# Power.net
KiCad netlist of a schematic drawn in Altium Designer
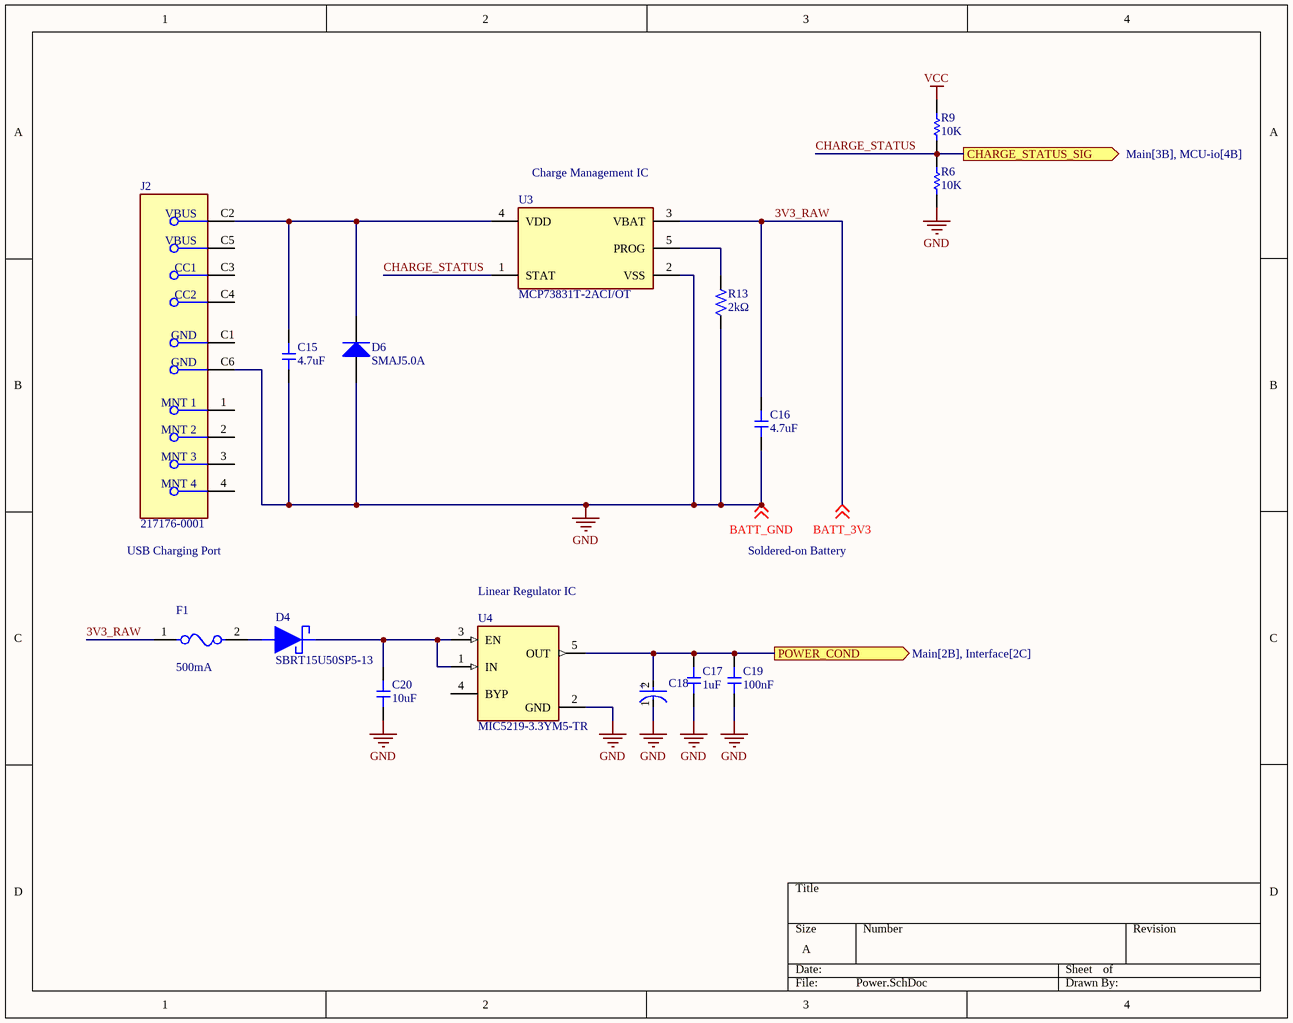
[diagram p0: Power.SchDoc]

(export (version "E")
  (design (tool "Eeschema 10.0.6"))
  (components
    (comp (ref "C15")
      (value "CL10A475KO8NNNC")
      (footprint "CAP-0603")
      (description "Capacitor, Ceramic (MLCC), 4.7uF, ±10%, 16V, X5R, ±10%, SMD 0603")
      (fields
        (field (name "JLCPCB BASIC PART") "Yes")
        (field (name "JLCPCB PART NUMBER") "C19666")
        (field (name "CAPACITANCE") "4.7uF")
      )
      (libsource (lib "JLCCapacitor") (part "CL10A475KO8NNNC"))
    )
    (comp (ref "C16")
      (value "CL10A475KO8NNNC")
      (footprint "CAP-0603")
      (description "Capacitor, Ceramic (MLCC), 4.7uF, ±10%, 16V, X5R, ±10%, SMD 0603")
      (fields
        (field (name "JLCPCB BASIC PART") "Yes")
        (field (name "JLCPCB PART NUMBER") "C19666")
        (field (name "CAPACITANCE") "4.7uF")
      )
      (libsource (lib "JLCCapacitor") (part "CL10A475KO8NNNC"))
    )
    (comp (ref "C17")
      (value "CL10A105KB8NNNC")
      (footprint "CAP-0603")
      (description "Capacitor, Ceramic (MLCC), 1uF, ±10%, 50V, X5R, ±10%, SMD 0603")
      (fields
        (field (name "JLCPCB BASIC PART") "Yes")
        (field (name "JLCPCB PART NUMBER") "C15849")
        (field (name "CAPACITANCE") "1uF")
      )
      (libsource (lib "JLCCapacitor") (part "CL10A105KB8NNNC"))
    )
    (comp (ref "C18")
      (value "293D106X9025B2TE3")
      (footprint "FP-293DB-MFG")
      (description "TANTALUM CAP 10000000 PF 10%")
      (fields (field (name "TOLERANCE") "10%"))
      (libsource (lib "Altium Content Vault") (part "203bc49f2ac43e59fd269a8c329ed05"))
    )
    (comp (ref "C19")
      (value "CC0603KRX7R9BB104")
      (footprint "CAP-0603")
      (description "Capacitor, Ceramic (MLCC), 100nF, ±10%, 50V, X7R, ±10%, SMD 0603")
      (fields
        (field (name "JLCPCB BASIC PART") "Yes")
        (field (name "CAPACITANCE") "100nF")
        (field (name "JLCPCB PART NUMBER") "C14663")
      )
      (libsource (lib "JLCCapacitor") (part "CC0603KRX7R9BB104"))
    )
    (comp (ref "C20")
      (value "CL10A106KP8NNNC")
      (footprint "CAP-0603")
      (description "Capacitor, Ceramic (MLCC), 10uF, ±10%, 10V, X5R, ±10%, SMD 0603")
      (fields
        (field (name "JLCPCB BASIC PART") "Yes")
        (field (name "JLCPCB PART NUMBER") "C19702")
        (field (name "CAPACITANCE") "10uF")
      )
      (libsource (lib "JLCCapacitor") (part "CL10A106KP8NNNC"))
    )
    (comp (ref "D4")
      (value "SBRT15U50SP5-13")
      (footprint "SBRT15U50SP5-13")
      (description "Reverse Polarity Protection")
      (fields (field (name "MANUFACTURER") "Diodes Incorporated"))
      (libsource (lib "DiodesAndFuses") (part "SBRT15U50SP5-13"))
    )
    (comp (ref "D6")
      (value "SMAJ5.0A")
      (footprint "BOUR-SMA-2_V")
      (fields (field (name "MANUFACTURER") "Bourns"))
      (libsource (lib "Altium Content Vault") (part "D-AK-2"))
    )
    (comp (ref "F1")
      (value "500mA")
      (footprint "FP-0466-MFG")
      (description "500mA Fuse")
      (fields
        (field (name "MANUFACTURER PART NUMBER") "0466.500NR")
        (field (name "OCTOPART") "https://octopart.com/0466.500nr-littelfuse-566004")
      )
      (libsource (lib "DiodesAndFuses") (part "0466.500NR"))
    )
    (comp (ref "J2")
      (value "217176-0001")
      (footprint "FP-217176-0001-MFG")
      (description "CONN RCPT TYPE C 24POS SMD RA")
      (libsource (lib "Altium Content Vault") (part "61257d644bc337d704aa790d3f53533"))
    )
    (comp (ref "R6")
      (value "10K")
      (footprint "RES_SM0603_YAGEORC_N")
      (description "RES 10K SM0603 YAGEO RC_L")
      (fields
        (field (name "MANUFACTURER") "Yageo")
        (field (name "MANUFACTURER PART NUMBER") "RC0603FR-0710KL")
      )
      (libsource (lib "ResistorCapsInductors") (part "RC0603FR-0710KL"))
    )
    (comp (ref "R9")
      (value "10K")
      (footprint "RES_SM0603_YAGEORC_N")
      (description "RES 10K SM0603 YAGEO RC_L")
      (fields
        (field (name "MANUFACTURER") "Yageo")
        (field (name "MANUFACTURER PART NUMBER") "RC0603FR-0710KL")
      )
      (libsource (lib "ResistorCapsInductors") (part "RC0603FR-0710KL"))
    )
    (comp (ref "R13")
      (value "0603WAF2001T5E")
      (footprint "RES-0603")
      (description "Resistor, 2kΩ, ±1%, 100mW, 75V, ±100ppm/℃, -55℃~+155℃, SMD 0603")
      (fields
        (field (name "MANUFACTURER") "Uniroyal")
        (field (name "JLCPCB PART NUMBER") "C22975")
        (field (name "RESISTANCE") "2kΩ")
      )
      (libsource (lib "JLCResistor") (part "0603WAF2001T5E"))
    )
    (comp (ref "U3")
      (value "MCP73831T-2ACI/OT")
      (footprint "FP-C04-091-OT-IPC_B")
      (description "IC CONTROLLR LI-ION 4.2V SOT23-5")
      (libsource (lib "Altium Content Vault") (part "61f5a3bb3429d9e0caadea342aa3b19"))
    )
    (comp (ref "U4")
      (value "MIC5219-3.3YM5-TR")
      (footprint "FP-SOT23-5LD-PL-1-IPC_C")
      (description "IC REG LINEAR 3.3V 500MA SOT23-5")
      (libsource (lib "Altium Content Vault") (part "16b36b16d6b7b40c29ab14718bc3058"))
    )
  )
  (nets
    (net (code "1") (name "/CHARGE_STATUS") (class "Default")
      (node (ref "R6") (pin "2") (pinfunction "2_2") (pintype "passive"))
      (node (ref "R9") (pin "1") (pinfunction "1_1") (pintype "passive"))
      (node (ref "U3") (pin "1") (pinfunction "STAT_1") (pintype "passive"))
    )
    (net (code "2") (name "/POWER_COND") (class "Default")
      (node (ref "C17") (pin "2") (pinfunction "2_2") (pintype "passive"))
      (node (ref "C18") (pin "2") (pinfunction "A_2") (pintype "passive"))
      (node (ref "C19") (pin "2") (pinfunction "2_2") (pintype "passive"))
      (node (ref "U4") (pin "5") (pinfunction "OUT_5") (pintype "output"))
    )
    (net (code "3") (name "BATT_3V3") (class "Default")
      (node (ref "C16") (pin "2") (pinfunction "2_2") (pintype "passive"))
      (node (ref "F1") (pin "1") (pinfunction "1_1") (pintype "passive"))
      (node (ref "U3") (pin "3") (pinfunction "VBAT_3") (pintype "power_in"))
    )
    (net (code "4") (name "BATT_GND") (class "Default")
      (node (ref "C15") (pin "1") (pinfunction "1_1") (pintype "passive"))
      (node (ref "C16") (pin "1") (pinfunction "1_1") (pintype "passive"))
      (node (ref "C17") (pin "1") (pinfunction "1_1") (pintype "passive"))
      (node (ref "C18") (pin "1") (pinfunction "C_1") (pintype "passive"))
      (node (ref "C19") (pin "1") (pinfunction "1_1") (pintype "passive"))
      (node (ref "C20") (pin "1") (pinfunction "1_1") (pintype "passive"))
      (node (ref "D6") (pin "1") (pinfunction "A_1") (pintype "passive"))
      (node (ref "J2") (pin "C6") (pinfunction "GND_C6") (pintype "power_in"))
      (node (ref "R13") (pin "1") (pinfunction "1_1") (pintype "passive"))
      (node (ref "R6") (pin "1") (pinfunction "1_1") (pintype "passive"))
      (node (ref "U3") (pin "2") (pinfunction "VSS_2") (pintype "power_in"))
      (node (ref "U4") (pin "2") (pinfunction "GND_2") (pintype "power_in"))
    )
    (net (code "5") (name "Net-(D4-Pad1)") (class "Default")
      (node (ref "D4") (pin "1") (pinfunction "1_1") (pintype "passive"))
      (node (ref "F1") (pin "2") (pinfunction "2_2") (pintype "passive"))
    )
    (net (code "6") (name "Net-(D6-K)") (class "Default")
      (node (ref "C15") (pin "2") (pinfunction "2_2") (pintype "passive"))
      (node (ref "D6") (pin "2") (pinfunction "K_2") (pintype "passive"))
      (node (ref "J2") (pin "C2") (pinfunction "VBUS_C2") (pintype "passive"))
      (node (ref "U3") (pin "4") (pinfunction "VDD_4") (pintype "power_in"))
    )
    (net (code "7") (name "Net-(U3-PROG)") (class "Default")
      (node (ref "R13") (pin "2") (pinfunction "2_2") (pintype "passive"))
      (node (ref "U3") (pin "5") (pinfunction "PROG_5") (pintype "passive"))
    )
    (net (code "8") (name "Net-(U4-EN)") (class "Default")
      (node (ref "C20") (pin "2") (pinfunction "2_2") (pintype "passive"))
      (node (ref "D4") (pin "2") (pinfunction "2_2") (pintype "passive"))
      (node (ref "U4") (pin "1") (pinfunction "IN_1") (pintype "input"))
      (node (ref "U4") (pin "3") (pinfunction "EN_3") (pintype "input"))
    )
    (net (code "9") (name "VCC") (class "Default")
      (node (ref "R9") (pin "2") (pinfunction "2_2") (pintype "passive"))
    )
    (net (code "10") (name "unconnected-(J2-CC1-PadC3)") (class "Default")
      (node (ref "J2") (pin "C3") (pinfunction "CC1_C3") (pintype "passive"))
    )
    (net (code "11") (name "unconnected-(J2-CC2-PadC4)") (class "Default")
      (node (ref "J2") (pin "C4") (pinfunction "CC2_C4") (pintype "passive"))
    )
    (net (code "12") (name "unconnected-(J2-GND-PadC1)") (class "Default")
      (node (ref "J2") (pin "C1") (pinfunction "GND_C1") (pintype "power_in"))
    )
    (net (code "13") (name "unconnected-(J2-MNT_1-Pad1)") (class "Default")
      (node (ref "J2") (pin "1") (pinfunction "MNT_1_1") (pintype "passive"))
    )
    (net (code "14") (name "unconnected-(J2-MNT_2-Pad2)") (class "Default")
      (node (ref "J2") (pin "2") (pinfunction "MNT_2_2") (pintype "passive"))
    )
    (net (code "15") (name "unconnected-(J2-MNT_3-Pad3)") (class "Default")
      (node (ref "J2") (pin "3") (pinfunction "MNT_3_3") (pintype "passive"))
    )
    (net (code "16") (name "unconnected-(J2-MNT_4-Pad4)") (class "Default")
      (node (ref "J2") (pin "4") (pinfunction "MNT_4_4") (pintype "passive"))
    )
    (net (code "17") (name "unconnected-(J2-VBUS-PadC5)") (class "Default")
      (node (ref "J2") (pin "C5") (pinfunction "VBUS_C5") (pintype "passive"))
    )
    (net (code "18") (name "unconnected-(U4-BYP-Pad4)") (class "Default")
      (node (ref "U4") (pin "4") (pinfunction "BYP_4") (pintype "passive"))
    )
  )
)
